# Sensors.net
KiCad netlist of a schematic drawn in Altium Designer
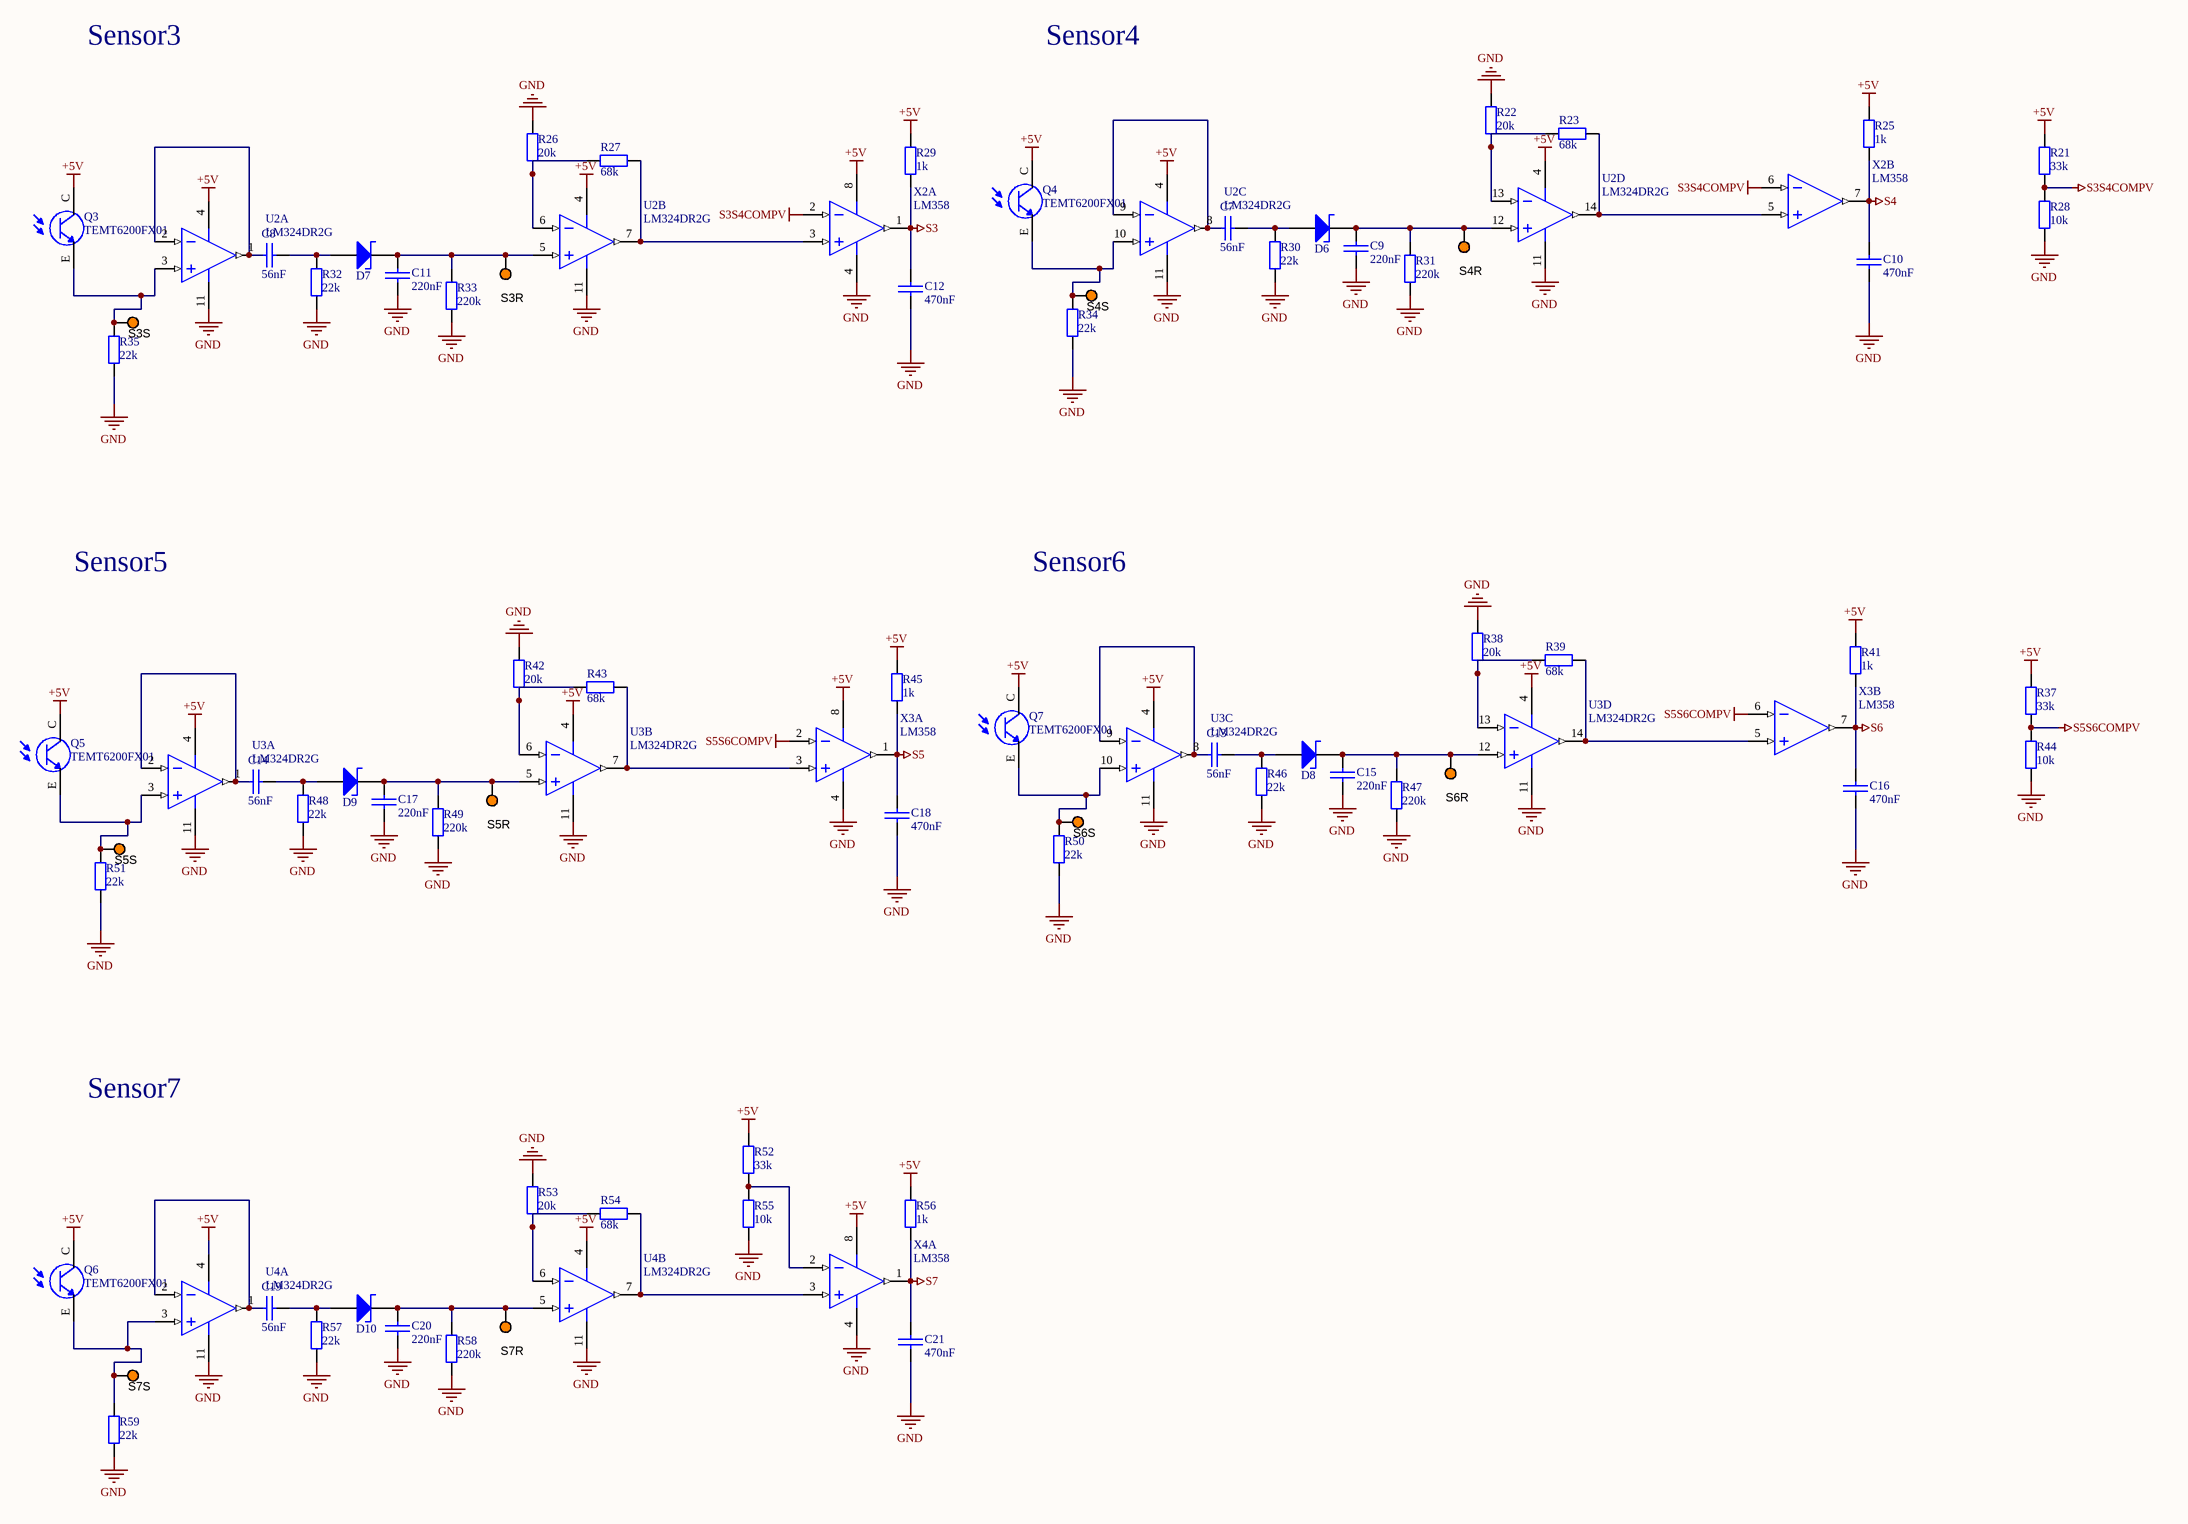
[diagram p0: Sensors.SchDoc]

(export (version "E")
  (design (tool "Eeschema 10.0.6"))
  (components
    (comp (ref "C7")
      (value "56nF")
      (footprint "0805 CAP")
      (description "SMT ceramic capacitor 0805 size")
      (libsource (lib "EE209_Library") (part "CerCap_SMT_0805"))
    )
    (comp (ref "C8")
      (value "56nF")
      (footprint "0805 CAP")
      (description "SMT ceramic capacitor 0805 size")
      (libsource (lib "EE209_Library") (part "CerCap_SMT_0805"))
    )
    (comp (ref "C9")
      (value "220nF")
      (footprint "0805 CAP")
      (description "SMT ceramic capacitor 0805 size")
      (libsource (lib "EE209_Library") (part "CerCap_SMT_0805"))
    )
    (comp (ref "C10")
      (value "470nF")
      (footprint "0805 CAP")
      (description "SMT ceramic capacitor 0805 size")
      (libsource (lib "EE209_Library") (part "CerCap_SMT_0805"))
    )
    (comp (ref "C11")
      (value "220nF")
      (footprint "0805 CAP")
      (description "SMT ceramic capacitor 0805 size")
      (libsource (lib "EE209_Library") (part "CerCap_SMT_0805"))
    )
    (comp (ref "C12")
      (value "470nF")
      (footprint "0805 CAP")
      (description "SMT ceramic capacitor 0805 size")
      (libsource (lib "EE209_Library") (part "CerCap_SMT_0805"))
    )
    (comp (ref "C13")
      (value "56nF")
      (footprint "0805 CAP")
      (description "SMT ceramic capacitor 0805 size")
      (libsource (lib "EE209_Library") (part "CerCap_SMT_0805"))
    )
    (comp (ref "C14")
      (value "56nF")
      (footprint "0805 CAP")
      (description "SMT ceramic capacitor 0805 size")
      (libsource (lib "EE209_Library") (part "CerCap_SMT_0805"))
    )
    (comp (ref "C15")
      (value "220nF")
      (footprint "0805 CAP")
      (description "SMT ceramic capacitor 0805 size")
      (libsource (lib "EE209_Library") (part "CerCap_SMT_0805"))
    )
    (comp (ref "C16")
      (value "470nF")
      (footprint "0805 CAP")
      (description "SMT ceramic capacitor 0805 size")
      (libsource (lib "EE209_Library") (part "CerCap_SMT_0805"))
    )
    (comp (ref "C17")
      (value "220nF")
      (footprint "0805 CAP")
      (description "SMT ceramic capacitor 0805 size")
      (libsource (lib "EE209_Library") (part "CerCap_SMT_0805"))
    )
    (comp (ref "C18")
      (value "470nF")
      (footprint "0805 CAP")
      (description "SMT ceramic capacitor 0805 size")
      (libsource (lib "EE209_Library") (part "CerCap_SMT_0805"))
    )
    (comp (ref "C19")
      (value "56nF")
      (footprint "0805 CAP")
      (description "SMT ceramic capacitor 0805 size")
      (libsource (lib "EE209_Library") (part "CerCap_SMT_0805"))
    )
    (comp (ref "C20")
      (value "220nF")
      (footprint "0805 CAP")
      (description "SMT ceramic capacitor 0805 size")
      (libsource (lib "EE209_Library") (part "CerCap_SMT_0805"))
    )
    (comp (ref "C21")
      (value "470nF")
      (footprint "0805 CAP")
      (description "SMT ceramic capacitor 0805 size")
      (libsource (lib "EE209_Library") (part "CerCap_SMT_0805"))
    )
    (comp (ref "D6")
      (value "BZT52H-B4V7")
      (footprint "SOD123")
      (description "SMT zener diode with SOD123 package")
      (fields
        (field (name "MANUFACTURER") "Nexperia USA Inc.")
        (field (name "MANUFACTURER PART NUMBER") "BZT52H-B4V7,115")
      )
      (libsource (lib "EE209_Library") (part "Zener_SMT_SOD123"))
    )
    (comp (ref "D7")
      (value "BZT52H-B4V7")
      (footprint "SOD123")
      (description "SMT zener diode with SOD123 package")
      (fields
        (field (name "MANUFACTURER") "Nexperia USA Inc.")
        (field (name "MANUFACTURER PART NUMBER") "BZT52H-B4V7,115")
      )
      (libsource (lib "EE209_Library") (part "Zener_SMT_SOD123"))
    )
    (comp (ref "D8")
      (value "BZT52H-B4V7")
      (footprint "SOD123")
      (description "SMT zener diode with SOD123 package")
      (fields
        (field (name "MANUFACTURER") "Nexperia USA Inc.")
        (field (name "MANUFACTURER PART NUMBER") "BZT52H-B4V7,115")
      )
      (libsource (lib "EE209_Library") (part "Zener_SMT_SOD123"))
    )
    (comp (ref "D9")
      (value "BZT52H-B4V7")
      (footprint "SOD123")
      (description "SMT zener diode with SOD123 package")
      (fields
        (field (name "MANUFACTURER") "Nexperia USA Inc.")
        (field (name "MANUFACTURER PART NUMBER") "BZT52H-B4V7,115")
      )
      (libsource (lib "EE209_Library") (part "Zener_SMT_SOD123"))
    )
    (comp (ref "D10")
      (value "BZT52H-B4V7")
      (footprint "SOD123")
      (description "SMT zener diode with SOD123 package")
      (fields
        (field (name "MANUFACTURER") "Nexperia USA Inc.")
        (field (name "MANUFACTURER PART NUMBER") "BZT52H-B4V7,115")
      )
      (libsource (lib "EE209_Library") (part "Zener_SMT_SOD123"))
    )
    (comp (ref "Q3")
      (value "TEMT6200FX01")
      (footprint "XDCR_TEMT6200FX01")
      (description "Phototransistors 550nm Top View 0805 (2012 Metric)")
      (fields (field (name "MF") "Vishay Semiconductor"))
      (libsource (lib "TEMT6200FX01") (part "TEMT6200FX01"))
    )
    (comp (ref "Q4")
      (value "TEMT6200FX01")
      (footprint "XDCR_TEMT6200FX01")
      (description "Phototransistors 550nm Top View 0805 (2012 Metric)")
      (fields (field (name "MF") "Vishay Semiconductor"))
      (libsource (lib "TEMT6200FX01") (part "TEMT6200FX01"))
    )
    (comp (ref "Q5")
      (value "TEMT6200FX01")
      (footprint "XDCR_TEMT6200FX01")
      (description "Phototransistors 550nm Top View 0805 (2012 Metric)")
      (fields (field (name "MF") "Vishay Semiconductor"))
      (libsource (lib "TEMT6200FX01") (part "TEMT6200FX01"))
    )
    (comp (ref "Q6")
      (value "TEMT6200FX01")
      (footprint "XDCR_TEMT6200FX01")
      (description "Phototransistors 550nm Top View 0805 (2012 Metric)")
      (fields (field (name "MF") "Vishay Semiconductor"))
      (libsource (lib "TEMT6200FX01") (part "TEMT6200FX01"))
    )
    (comp (ref "Q7")
      (value "TEMT6200FX01")
      (footprint "XDCR_TEMT6200FX01")
      (description "Phototransistors 550nm Top View 0805 (2012 Metric)")
      (fields (field (name "MF") "Vishay Semiconductor"))
      (libsource (lib "TEMT6200FX01") (part "TEMT6200FX01"))
    )
    (comp (ref "R21")
      (value "33k")
      (footprint "0805 RES")
      (description "0805 resistor")
      (fields (field (name "PUBLISHER") "Altium Limited"))
      (libsource (lib "") (part "Res_SMT_0805_2"))
    )
    (comp (ref "R22")
      (value "20k")
      (footprint "0805 RES")
      (description "0805 resistor")
      (fields (field (name "PUBLISHER") "Altium Limited"))
      (libsource (lib "EE209_Library") (part "Res_SMT_0805"))
    )
    (comp (ref "R23")
      (value "68k")
      (footprint "0805 RES")
      (description "0805 resistor")
      (fields (field (name "PUBLISHER") "Altium Limited"))
      (libsource (lib "") (part "Res_SMT_0805_1"))
    )
    (comp (ref "R25")
      (value "1k")
      (footprint "0805 RES")
      (description "0805 resistor")
      (fields (field (name "PUBLISHER") "Altium Limited"))
      (libsource (lib "") (part "Res_SMT_0805_2"))
    )
    (comp (ref "R26")
      (value "20k")
      (footprint "0805 RES")
      (description "0805 resistor")
      (fields (field (name "PUBLISHER") "Altium Limited"))
      (libsource (lib "EE209_Library") (part "Res_SMT_0805"))
    )
    (comp (ref "R27")
      (value "68k")
      (footprint "0805 RES")
      (description "0805 resistor")
      (fields (field (name "PUBLISHER") "Altium Limited"))
      (libsource (lib "") (part "Res_SMT_0805_1"))
    )
    (comp (ref "R28")
      (value "10k")
      (footprint "0805 RES")
      (description "0805 resistor")
      (fields (field (name "PUBLISHER") "Altium Limited"))
      (libsource (lib "") (part "Res_SMT_0805_2"))
    )
    (comp (ref "R29")
      (value "1k")
      (footprint "0805 RES")
      (description "0805 resistor")
      (fields (field (name "PUBLISHER") "Altium Limited"))
      (libsource (lib "") (part "Res_SMT_0805_2"))
    )
    (comp (ref "R30")
      (value "22k")
      (footprint "0805 RES")
      (description "0805 resistor")
      (fields (field (name "PUBLISHER") "Altium Limited"))
      (libsource (lib "EE209_Library") (part "Res_SMT_0805"))
    )
    (comp (ref "R31")
      (value "220k")
      (footprint "0805 RES")
      (description "0805 resistor")
      (fields (field (name "PUBLISHER") "Altium Limited"))
      (libsource (lib "EE209_Library") (part "Res_SMT_0805"))
    )
    (comp (ref "R32")
      (value "22k")
      (footprint "0805 RES")
      (description "0805 resistor")
      (fields (field (name "PUBLISHER") "Altium Limited"))
      (libsource (lib "EE209_Library") (part "Res_SMT_0805"))
    )
    (comp (ref "R33")
      (value "220k")
      (footprint "0805 RES")
      (description "0805 resistor")
      (fields (field (name "PUBLISHER") "Altium Limited"))
      (libsource (lib "EE209_Library") (part "Res_SMT_0805"))
    )
    (comp (ref "R34")
      (value "22k")
      (footprint "0805 RES")
      (description "0805 resistor")
      (fields (field (name "PUBLISHER") "Altium Limited"))
      (libsource (lib "EE209_Library") (part "Res_SMT_0805"))
    )
    (comp (ref "R35")
      (value "22k")
      (footprint "0805 RES")
      (description "0805 resistor")
      (fields (field (name "PUBLISHER") "Altium Limited"))
      (libsource (lib "EE209_Library") (part "Res_SMT_0805"))
    )
    (comp (ref "R37")
      (value "33k")
      (footprint "0805 RES")
      (description "0805 resistor")
      (fields (field (name "PUBLISHER") "Altium Limited"))
      (libsource (lib "") (part "Res_SMT_0805_2"))
    )
    (comp (ref "R38")
      (value "20k")
      (footprint "0805 RES")
      (description "0805 resistor")
      (fields (field (name "PUBLISHER") "Altium Limited"))
      (libsource (lib "EE209_Library") (part "Res_SMT_0805"))
    )
    (comp (ref "R39")
      (value "68k")
      (footprint "0805 RES")
      (description "0805 resistor")
      (fields (field (name "PUBLISHER") "Altium Limited"))
      (libsource (lib "") (part "Res_SMT_0805_1"))
    )
    (comp (ref "R41")
      (value "1k")
      (footprint "0805 RES")
      (description "0805 resistor")
      (fields (field (name "PUBLISHER") "Altium Limited"))
      (libsource (lib "") (part "Res_SMT_0805_2"))
    )
    (comp (ref "R42")
      (value "20k")
      (footprint "0805 RES")
      (description "0805 resistor")
      (fields (field (name "PUBLISHER") "Altium Limited"))
      (libsource (lib "EE209_Library") (part "Res_SMT_0805"))
    )
    (comp (ref "R43")
      (value "68k")
      (footprint "0805 RES")
      (description "0805 resistor")
      (fields (field (name "PUBLISHER") "Altium Limited"))
      (libsource (lib "") (part "Res_SMT_0805_1"))
    )
    (comp (ref "R44")
      (value "10k")
      (footprint "0805 RES")
      (description "0805 resistor")
      (fields (field (name "PUBLISHER") "Altium Limited"))
      (libsource (lib "") (part "Res_SMT_0805_2"))
    )
    (comp (ref "R45")
      (value "1k")
      (footprint "0805 RES")
      (description "0805 resistor")
      (fields (field (name "PUBLISHER") "Altium Limited"))
      (libsource (lib "") (part "Res_SMT_0805_2"))
    )
    (comp (ref "R46")
      (value "22k")
      (footprint "0805 RES")
      (description "0805 resistor")
      (fields (field (name "PUBLISHER") "Altium Limited"))
      (libsource (lib "EE209_Library") (part "Res_SMT_0805"))
    )
    (comp (ref "R47")
      (value "220k")
      (footprint "0805 RES")
      (description "0805 resistor")
      (fields (field (name "PUBLISHER") "Altium Limited"))
      (libsource (lib "EE209_Library") (part "Res_SMT_0805"))
    )
    (comp (ref "R48")
      (value "22k")
      (footprint "0805 RES")
      (description "0805 resistor")
      (fields (field (name "PUBLISHER") "Altium Limited"))
      (libsource (lib "EE209_Library") (part "Res_SMT_0805"))
    )
    (comp (ref "R49")
      (value "220k")
      (footprint "0805 RES")
      (description "0805 resistor")
      (fields (field (name "PUBLISHER") "Altium Limited"))
      (libsource (lib "EE209_Library") (part "Res_SMT_0805"))
    )
    (comp (ref "R50")
      (value "22k")
      (footprint "0805 RES")
      (description "0805 resistor")
      (fields (field (name "PUBLISHER") "Altium Limited"))
      (libsource (lib "EE209_Library") (part "Res_SMT_0805"))
    )
    (comp (ref "R51")
      (value "22k")
      (footprint "0805 RES")
      (description "0805 resistor")
      (fields (field (name "PUBLISHER") "Altium Limited"))
      (libsource (lib "EE209_Library") (part "Res_SMT_0805"))
    )
    (comp (ref "R52")
      (value "33k")
      (footprint "0805 RES")
      (description "0805 resistor")
      (fields (field (name "PUBLISHER") "Altium Limited"))
      (libsource (lib "") (part "Res_SMT_0805_2"))
    )
    (comp (ref "R53")
      (value "20k")
      (footprint "0805 RES")
      (description "0805 resistor")
      (fields (field (name "PUBLISHER") "Altium Limited"))
      (libsource (lib "EE209_Library") (part "Res_SMT_0805"))
    )
    (comp (ref "R54")
      (value "68k")
      (footprint "0805 RES")
      (description "0805 resistor")
      (fields (field (name "PUBLISHER") "Altium Limited"))
      (libsource (lib "") (part "Res_SMT_0805_1"))
    )
    (comp (ref "R55")
      (value "10k")
      (footprint "0805 RES")
      (description "0805 resistor")
      (fields (field (name "PUBLISHER") "Altium Limited"))
      (libsource (lib "") (part "Res_SMT_0805_2"))
    )
    (comp (ref "R56")
      (value "1k")
      (footprint "0805 RES")
      (description "0805 resistor")
      (fields (field (name "PUBLISHER") "Altium Limited"))
      (libsource (lib "") (part "Res_SMT_0805_2"))
    )
    (comp (ref "R57")
      (value "22k")
      (footprint "0805 RES")
      (description "0805 resistor")
      (fields (field (name "PUBLISHER") "Altium Limited"))
      (libsource (lib "EE209_Library") (part "Res_SMT_0805"))
    )
    (comp (ref "R58")
      (value "220k")
      (footprint "0805 RES")
      (description "0805 resistor")
      (fields (field (name "PUBLISHER") "Altium Limited"))
      (libsource (lib "EE209_Library") (part "Res_SMT_0805"))
    )
    (comp (ref "R59")
      (value "22k")
      (footprint "0805 RES")
      (description "0805 resistor")
      (fields (field (name "PUBLISHER") "Altium Limited"))
      (libsource (lib "EE209_Library") (part "Res_SMT_0805"))
    )
    (comp (ref "S3R")
      (value "5003")
      (footprint "TP_TH")
      (description "Test Point, Orange, 1-Pin THD, RoHS")
      (libsource (lib "EE209_Library") (part "TestPoint"))
    )
    (comp (ref "S3S")
      (value "5003")
      (footprint "TP_TH")
      (description "Test Point, Orange, 1-Pin THD, RoHS")
      (libsource (lib "EE209_Library") (part "TestPoint"))
    )
    (comp (ref "S4R")
      (value "5003")
      (footprint "TP_TH")
      (description "Test Point, Orange, 1-Pin THD, RoHS")
      (libsource (lib "EE209_Library") (part "TestPoint"))
    )
    (comp (ref "S4S")
      (value "5003")
      (footprint "TP_TH")
      (description "Test Point, Orange, 1-Pin THD, RoHS")
      (libsource (lib "EE209_Library") (part "TestPoint"))
    )
    (comp (ref "S5R")
      (value "5003")
      (footprint "TP_TH")
      (description "Test Point, Orange, 1-Pin THD, RoHS")
      (libsource (lib "EE209_Library") (part "TestPoint"))
    )
    (comp (ref "S5S")
      (value "5003")
      (footprint "TP_TH")
      (description "Test Point, Orange, 1-Pin THD, RoHS")
      (libsource (lib "EE209_Library") (part "TestPoint"))
    )
    (comp (ref "S6R")
      (value "5003")
      (footprint "TP_TH")
      (description "Test Point, Orange, 1-Pin THD, RoHS")
      (libsource (lib "EE209_Library") (part "TestPoint"))
    )
    (comp (ref "S6S")
      (value "5003")
      (footprint "TP_TH")
      (description "Test Point, Orange, 1-Pin THD, RoHS")
      (libsource (lib "EE209_Library") (part "TestPoint"))
    )
    (comp (ref "S7R")
      (value "5003")
      (footprint "TP_TH")
      (description "Test Point, Orange, 1-Pin THD, RoHS")
      (libsource (lib "EE209_Library") (part "TestPoint"))
    )
    (comp (ref "S7S")
      (value "5003")
      (footprint "TP_TH")
      (description "Test Point, Orange, 1-Pin THD, RoHS")
      (libsource (lib "EE209_Library") (part "TestPoint"))
    )
    (comp (ref "U2")
      (value "LM324DR2G")
      (footprint "SOIC-14")
      (fields (field (name "MANUFACTURER") "On Semiconductor"))
      (libsource (lib "EE209_Library") (part "LM324DR_SMT_SOIC16"))
    )
    (comp (ref "U3")
      (value "LM324DR2G")
      (footprint "SOIC-14")
      (fields (field (name "MANUFACTURER") "On Semiconductor"))
      (libsource (lib "EE209_Library") (part "LM324DR_SMT_SOIC16"))
    )
    (comp (ref "U4")
      (value "LM324DR2G")
      (footprint "SOIC-14")
      (fields (field (name "MANUFACTURER") "On Semiconductor"))
      (libsource (lib "EE209_Library") (part "LM324DR_SMT_SOIC16"))
    )
    (comp (ref "X2")
      (value "LM358")
      (footprint "SO - 8")
      (description "IC OPAMP 8SOIC")
      (libsource (lib "EE209_Library") (part "LM358_SMT_SOIC8"))
    )
    (comp (ref "X3")
      (value "LM358")
      (footprint "SO - 8")
      (description "IC OPAMP 8SOIC")
      (libsource (lib "EE209_Library") (part "LM358_SMT_SOIC8"))
    )
    (comp (ref "X4")
      (value "LM358")
      (footprint "SO - 8")
      (description "IC OPAMP 8SOIC")
      (libsource (lib "EE209_Library") (part "LM358_SMT_SOIC8"))
    )
  )
  (nets
    (net (code "1") (name "+5V") (class "Default")
      (node (ref "Q3") (pin "C") (pinfunction "C_C") (pintype "passive"))
      (node (ref "Q4") (pin "C") (pinfunction "C_C") (pintype "passive"))
      (node (ref "Q5") (pin "C") (pinfunction "C_C") (pintype "passive"))
      (node (ref "Q6") (pin "C") (pinfunction "C_C") (pintype "passive"))
      (node (ref "Q7") (pin "C") (pinfunction "C_C") (pintype "passive"))
      (node (ref "R21") (pin "1") (pinfunction "1_1") (pintype "passive"))
      (node (ref "R25") (pin "1") (pinfunction "1_1") (pintype "passive"))
      (node (ref "R29") (pin "1") (pinfunction "1_1") (pintype "passive"))
      (node (ref "R37") (pin "1") (pinfunction "1_1") (pintype "passive"))
      (node (ref "R41") (pin "1") (pinfunction "1_1") (pintype "passive"))
      (node (ref "R45") (pin "1") (pinfunction "1_1") (pintype "passive"))
      (node (ref "R52") (pin "1") (pinfunction "1_1") (pintype "passive"))
      (node (ref "R56") (pin "1") (pinfunction "1_1") (pintype "passive"))
      (node (ref "U2") (pin "4") (pinfunction "VCC_4") (pintype "power_in"))
      (node (ref "U3") (pin "4") (pinfunction "VCC_4") (pintype "power_in"))
      (node (ref "U4") (pin "4") (pinfunction "VCC_4") (pintype "power_in"))
      (node (ref "X2") (pin "8") (pinfunction "VDD_8") (pintype "power_in"))
      (node (ref "X3") (pin "8") (pinfunction "VDD_8") (pintype "power_in"))
      (node (ref "X4") (pin "8") (pinfunction "VDD_8") (pintype "power_in"))
    )
    (net (code "2") (name "GND") (class "Default")
      (node (ref "C10") (pin "2") (pinfunction "2_2") (pintype "passive"))
      (node (ref "C11") (pin "2") (pinfunction "2_2") (pintype "passive"))
      (node (ref "C12") (pin "2") (pinfunction "2_2") (pintype "passive"))
      (node (ref "C15") (pin "2") (pinfunction "2_2") (pintype "passive"))
      (node (ref "C16") (pin "2") (pinfunction "2_2") (pintype "passive"))
      (node (ref "C17") (pin "2") (pinfunction "2_2") (pintype "passive"))
      (node (ref "C18") (pin "2") (pinfunction "2_2") (pintype "passive"))
      (node (ref "C20") (pin "2") (pinfunction "2_2") (pintype "passive"))
      (node (ref "C21") (pin "2") (pinfunction "2_2") (pintype "passive"))
      (node (ref "C9") (pin "2") (pinfunction "2_2") (pintype "passive"))
      (node (ref "R22") (pin "2") (pinfunction "2_2") (pintype "passive"))
      (node (ref "R26") (pin "2") (pinfunction "2_2") (pintype "passive"))
      (node (ref "R28") (pin "2") (pinfunction "2_2") (pintype "passive"))
      (node (ref "R30") (pin "1") (pinfunction "1_1") (pintype "passive"))
      (node (ref "R31") (pin "1") (pinfunction "1_1") (pintype "passive"))
      (node (ref "R32") (pin "1") (pinfunction "1_1") (pintype "passive"))
      (node (ref "R33") (pin "1") (pinfunction "1_1") (pintype "passive"))
      (node (ref "R34") (pin "1") (pinfunction "1_1") (pintype "passive"))
      (node (ref "R35") (pin "1") (pinfunction "1_1") (pintype "passive"))
      (node (ref "R38") (pin "2") (pinfunction "2_2") (pintype "passive"))
      (node (ref "R42") (pin "2") (pinfunction "2_2") (pintype "passive"))
      (node (ref "R44") (pin "2") (pinfunction "2_2") (pintype "passive"))
      (node (ref "R46") (pin "1") (pinfunction "1_1") (pintype "passive"))
      (node (ref "R47") (pin "1") (pinfunction "1_1") (pintype "passive"))
      (node (ref "R48") (pin "1") (pinfunction "1_1") (pintype "passive"))
      (node (ref "R49") (pin "1") (pinfunction "1_1") (pintype "passive"))
      (node (ref "R50") (pin "1") (pinfunction "1_1") (pintype "passive"))
      (node (ref "R51") (pin "1") (pinfunction "1_1") (pintype "passive"))
      (node (ref "R53") (pin "2") (pinfunction "2_2") (pintype "passive"))
      (node (ref "R55") (pin "2") (pinfunction "2_2") (pintype "passive"))
      (node (ref "R57") (pin "1") (pinfunction "1_1") (pintype "passive"))
      (node (ref "R58") (pin "1") (pinfunction "1_1") (pintype "passive"))
      (node (ref "R59") (pin "1") (pinfunction "1_1") (pintype "passive"))
      (node (ref "U2") (pin "11") (pinfunction "VEE/GND_11") (pintype "power_in"))
      (node (ref "U3") (pin "11") (pinfunction "VEE/GND_11") (pintype "power_in"))
      (node (ref "U4") (pin "11") (pinfunction "VEE/GND_11") (pintype "power_in"))
      (node (ref "X2") (pin "4") (pinfunction "VSS_4") (pintype "power_in"))
      (node (ref "X3") (pin "4") (pinfunction "VSS_4") (pintype "power_in"))
      (node (ref "X4") (pin "4") (pinfunction "VSS_4") (pintype "power_in"))
    )
    (net (code "3") (name "Net-(D6-A)") (class "Default")
      (node (ref "C7") (pin "2") (pinfunction "2_2") (pintype "passive"))
      (node (ref "D6") (pin "1") (pinfunction "A_1") (pintype "passive"))
      (node (ref "R30") (pin "2") (pinfunction "2_2") (pintype "passive"))
    )
    (net (code "4") (name "Net-(D6-K)") (class "Default")
      (node (ref "C9") (pin "1") (pinfunction "1_1") (pintype "passive"))
      (node (ref "D6") (pin "2") (pinfunction "K_2") (pintype "passive"))
      (node (ref "R31") (pin "2") (pinfunction "2_2") (pintype "passive"))
      (node (ref "S4R") (pin "1") (pinfunction "1_1") (pintype "passive"))
      (node (ref "U2") (pin "12") (pinfunction "IN4+_12") (pintype "input"))
    )
    (net (code "5") (name "Net-(D7-A)") (class "Default")
      (node (ref "C8") (pin "2") (pinfunction "2_2") (pintype "passive"))
      (node (ref "D7") (pin "1") (pinfunction "A_1") (pintype "passive"))
      (node (ref "R32") (pin "2") (pinfunction "2_2") (pintype "passive"))
    )
    (net (code "6") (name "Net-(D7-K)") (class "Default")
      (node (ref "C11") (pin "1") (pinfunction "1_1") (pintype "passive"))
      (node (ref "D7") (pin "2") (pinfunction "K_2") (pintype "passive"))
      (node (ref "R33") (pin "2") (pinfunction "2_2") (pintype "passive"))
      (node (ref "S3R") (pin "1") (pinfunction "1_1") (pintype "passive"))
      (node (ref "U2") (pin "5") (pinfunction "IN2+_5") (pintype "input"))
    )
    (net (code "7") (name "Net-(D8-A)") (class "Default")
      (node (ref "C13") (pin "2") (pinfunction "2_2") (pintype "passive"))
      (node (ref "D8") (pin "1") (pinfunction "A_1") (pintype "passive"))
      (node (ref "R46") (pin "2") (pinfunction "2_2") (pintype "passive"))
    )
    (net (code "8") (name "Net-(D8-K)") (class "Default")
      (node (ref "C15") (pin "1") (pinfunction "1_1") (pintype "passive"))
      (node (ref "D8") (pin "2") (pinfunction "K_2") (pintype "passive"))
      (node (ref "R47") (pin "2") (pinfunction "2_2") (pintype "passive"))
      (node (ref "S6R") (pin "1") (pinfunction "1_1") (pintype "passive"))
      (node (ref "U3") (pin "12") (pinfunction "IN4+_12") (pintype "input"))
    )
    (net (code "9") (name "Net-(D9-A)") (class "Default")
      (node (ref "C14") (pin "2") (pinfunction "2_2") (pintype "passive"))
      (node (ref "D9") (pin "1") (pinfunction "A_1") (pintype "passive"))
      (node (ref "R48") (pin "2") (pinfunction "2_2") (pintype "passive"))
    )
    (net (code "10") (name "Net-(D9-K)") (class "Default")
      (node (ref "C17") (pin "1") (pinfunction "1_1") (pintype "passive"))
      (node (ref "D9") (pin "2") (pinfunction "K_2") (pintype "passive"))
      (node (ref "R49") (pin "2") (pinfunction "2_2") (pintype "passive"))
      (node (ref "S5R") (pin "1") (pinfunction "1_1") (pintype "passive"))
      (node (ref "U3") (pin "5") (pinfunction "IN2+_5") (pintype "input"))
    )
    (net (code "11") (name "Net-(D10-A)") (class "Default")
      (node (ref "C19") (pin "2") (pinfunction "2_2") (pintype "passive"))
      (node (ref "D10") (pin "1") (pinfunction "A_1") (pintype "passive"))
      (node (ref "R57") (pin "2") (pinfunction "2_2") (pintype "passive"))
    )
    (net (code "12") (name "Net-(D10-K)") (class "Default")
      (node (ref "C20") (pin "1") (pinfunction "1_1") (pintype "passive"))
      (node (ref "D10") (pin "2") (pinfunction "K_2") (pintype "passive"))
      (node (ref "R58") (pin "2") (pinfunction "2_2") (pintype "passive"))
      (node (ref "S7R") (pin "1") (pinfunction "1_1") (pintype "passive"))
      (node (ref "U4") (pin "5") (pinfunction "IN2+_5") (pintype "input"))
    )
    (net (code "13") (name "Net-(U2A-IN1+)") (class "Default")
      (node (ref "Q3") (pin "E") (pinfunction "E_E") (pintype "passive"))
      (node (ref "R35") (pin "2") (pinfunction "2_2") (pintype "passive"))
      (node (ref "S3S") (pin "1") (pinfunction "1_1") (pintype "passive"))
      (node (ref "U2") (pin "3") (pinfunction "IN1+_3") (pintype "input"))
    )
    (net (code "14") (name "Net-(U2A-IN1-)") (class "Default")
      (node (ref "C8") (pin "1") (pinfunction "1_1") (pintype "passive"))
      (node (ref "U2") (pin "1") (pinfunction "OUT1_1") (pintype "output"))
      (node (ref "U2") (pin "2") (pinfunction "IN1-_2") (pintype "input"))
    )
    (net (code "15") (name "Net-(U2B-IN2-)") (class "Default")
      (node (ref "R26") (pin "1") (pinfunction "1_1") (pintype "passive"))
      (node (ref "R27") (pin "2") (pinfunction "2_2") (pintype "passive"))
      (node (ref "U2") (pin "6") (pinfunction "IN2-_6") (pintype "input"))
    )
    (net (code "16") (name "Net-(U2B-OUT2)") (class "Default")
      (node (ref "R27") (pin "1") (pinfunction "1_1") (pintype "passive"))
      (node (ref "U2") (pin "7") (pinfunction "OUT2_7") (pintype "output"))
      (node (ref "X2") (pin "3") (pinfunction "VINA+_3") (pintype "input"))
    )
    (net (code "17") (name "Net-(U2C-IN3+)") (class "Default")
      (node (ref "Q4") (pin "E") (pinfunction "E_E") (pintype "passive"))
      (node (ref "R34") (pin "2") (pinfunction "2_2") (pintype "passive"))
      (node (ref "S4S") (pin "1") (pinfunction "1_1") (pintype "passive"))
      (node (ref "U2") (pin "10") (pinfunction "IN3+_10") (pintype "input"))
    )
    (net (code "18") (name "Net-(U2C-IN3-)") (class "Default")
      (node (ref "C7") (pin "1") (pinfunction "1_1") (pintype "passive"))
      (node (ref "U2") (pin "8") (pinfunction "OUT3_8") (pintype "output"))
      (node (ref "U2") (pin "9") (pinfunction "IN3-_9") (pintype "input"))
    )
    (net (code "19") (name "Net-(U2D-IN4-)") (class "Default")
      (node (ref "R22") (pin "1") (pinfunction "1_1") (pintype "passive"))
      (node (ref "R23") (pin "2") (pinfunction "2_2") (pintype "passive"))
      (node (ref "U2") (pin "13") (pinfunction "IN4-_13") (pintype "input"))
    )
    (net (code "20") (name "Net-(U2D-OUT4)") (class "Default")
      (node (ref "R23") (pin "1") (pinfunction "1_1") (pintype "passive"))
      (node (ref "U2") (pin "14") (pinfunction "OUT4_14") (pintype "output"))
      (node (ref "X2") (pin "5") (pinfunction "VINA+_5") (pintype "input"))
    )
    (net (code "21") (name "Net-(U3A-IN1+)") (class "Default")
      (node (ref "Q5") (pin "E") (pinfunction "E_E") (pintype "passive"))
      (node (ref "R51") (pin "2") (pinfunction "2_2") (pintype "passive"))
      (node (ref "S5S") (pin "1") (pinfunction "1_1") (pintype "passive"))
      (node (ref "U3") (pin "3") (pinfunction "IN1+_3") (pintype "input"))
    )
    (net (code "22") (name "Net-(U3A-IN1-)") (class "Default")
      (node (ref "C14") (pin "1") (pinfunction "1_1") (pintype "passive"))
      (node (ref "U3") (pin "1") (pinfunction "OUT1_1") (pintype "output"))
      (node (ref "U3") (pin "2") (pinfunction "IN1-_2") (pintype "input"))
    )
    (net (code "23") (name "Net-(U3B-IN2-)") (class "Default")
      (node (ref "R42") (pin "1") (pinfunction "1_1") (pintype "passive"))
      (node (ref "R43") (pin "2") (pinfunction "2_2") (pintype "passive"))
      (node (ref "U3") (pin "6") (pinfunction "IN2-_6") (pintype "input"))
    )
    (net (code "24") (name "Net-(U3B-OUT2)") (class "Default")
      (node (ref "R43") (pin "1") (pinfunction "1_1") (pintype "passive"))
      (node (ref "U3") (pin "7") (pinfunction "OUT2_7") (pintype "output"))
      (node (ref "X3") (pin "3") (pinfunction "VINA+_3") (pintype "input"))
    )
    (net (code "25") (name "Net-(U3C-IN3+)") (class "Default")
      (node (ref "Q7") (pin "E") (pinfunction "E_E") (pintype "passive"))
      (node (ref "R50") (pin "2") (pinfunction "2_2") (pintype "passive"))
      (node (ref "S6S") (pin "1") (pinfunction "1_1") (pintype "passive"))
      (node (ref "U3") (pin "10") (pinfunction "IN3+_10") (pintype "input"))
    )
    (net (code "26") (name "Net-(U3C-IN3-)") (class "Default")
      (node (ref "C13") (pin "1") (pinfunction "1_1") (pintype "passive"))
      (node (ref "U3") (pin "8") (pinfunction "OUT3_8") (pintype "output"))
      (node (ref "U3") (pin "9") (pinfunction "IN3-_9") (pintype "input"))
    )
    (net (code "27") (name "Net-(U3D-IN4-)") (class "Default")
      (node (ref "R38") (pin "1") (pinfunction "1_1") (pintype "passive"))
      (node (ref "R39") (pin "2") (pinfunction "2_2") (pintype "passive"))
      (node (ref "U3") (pin "13") (pinfunction "IN4-_13") (pintype "input"))
    )
    (net (code "28") (name "Net-(U3D-OUT4)") (class "Default")
      (node (ref "R39") (pin "1") (pinfunction "1_1") (pintype "passive"))
      (node (ref "U3") (pin "14") (pinfunction "OUT4_14") (pintype "output"))
      (node (ref "X3") (pin "5") (pinfunction "VINA+_5") (pintype "input"))
    )
    (net (code "29") (name "Net-(U4A-IN1+)") (class "Default")
      (node (ref "Q6") (pin "E") (pinfunction "E_E") (pintype "passive"))
      (node (ref "R59") (pin "2") (pinfunction "2_2") (pintype "passive"))
      (node (ref "S7S") (pin "1") (pinfunction "1_1") (pintype "passive"))
      (node (ref "U4") (pin "3") (pinfunction "IN1+_3") (pintype "input"))
    )
    (net (code "30") (name "Net-(U4A-IN1-)") (class "Default")
      (node (ref "C19") (pin "1") (pinfunction "1_1") (pintype "passive"))
      (node (ref "U4") (pin "1") (pinfunction "OUT1_1") (pintype "output"))
      (node (ref "U4") (pin "2") (pinfunction "IN1-_2") (pintype "input"))
    )
    (net (code "31") (name "Net-(U4B-IN2-)") (class "Default")
      (node (ref "R53") (pin "1") (pinfunction "1_1") (pintype "passive"))
      (node (ref "R54") (pin "2") (pinfunction "2_2") (pintype "passive"))
      (node (ref "U4") (pin "6") (pinfunction "IN2-_6") (pintype "input"))
    )
    (net (code "32") (name "Net-(U4B-OUT2)") (class "Default")
      (node (ref "R54") (pin "1") (pinfunction "1_1") (pintype "passive"))
      (node (ref "U4") (pin "7") (pinfunction "OUT2_7") (pintype "output"))
      (node (ref "X4") (pin "3") (pinfunction "VINA+_3") (pintype "input"))
    )
    (net (code "33") (name "Net-(X4A-VINA-)") (class "Default")
      (node (ref "R52") (pin "2") (pinfunction "2_2") (pintype "passive"))
      (node (ref "R55") (pin "1") (pinfunction "1_1") (pintype "passive"))
      (node (ref "X4") (pin "2") (pinfunction "VINA-_2") (pintype "input"))
    )
    (net (code "34") (name "S3") (class "Default")
      (node (ref "C12") (pin "1") (pinfunction "1_1") (pintype "passive"))
      (node (ref "R29") (pin "2") (pinfunction "2_2") (pintype "passive"))
      (node (ref "X2") (pin "1") (pinfunction "VOUTA_1") (pintype "output"))
    )
    (net (code "35") (name "S3S4COMPV") (class "Default")
      (node (ref "R21") (pin "2") (pinfunction "2_2") (pintype "passive"))
      (node (ref "R28") (pin "1") (pinfunction "1_1") (pintype "passive"))
      (node (ref "X2") (pin "2") (pinfunction "VINA-_2") (pintype "input"))
      (node (ref "X2") (pin "6") (pinfunction "VINA-_6") (pintype "input"))
    )
    (net (code "36") (name "S4") (class "Default")
      (node (ref "C10") (pin "1") (pinfunction "1_1") (pintype "passive"))
      (node (ref "R25") (pin "2") (pinfunction "2_2") (pintype "passive"))
      (node (ref "X2") (pin "7") (pinfunction "VOUTA_7") (pintype "output"))
    )
    (net (code "37") (name "S5") (class "Default")
      (node (ref "C18") (pin "1") (pinfunction "1_1") (pintype "passive"))
      (node (ref "R45") (pin "2") (pinfunction "2_2") (pintype "passive"))
      (node (ref "X3") (pin "1") (pinfunction "VOUTA_1") (pintype "output"))
    )
    (net (code "38") (name "S5S6COMPV") (class "Default")
      (node (ref "R37") (pin "2") (pinfunction "2_2") (pintype "passive"))
      (node (ref "R44") (pin "1") (pinfunction "1_1") (pintype "passive"))
      (node (ref "X3") (pin "2") (pinfunction "VINA-_2") (pintype "input"))
      (node (ref "X3") (pin "6") (pinfunction "VINA-_6") (pintype "input"))
    )
    (net (code "39") (name "S6") (class "Default")
      (node (ref "C16") (pin "1") (pinfunction "1_1") (pintype "passive"))
      (node (ref "R41") (pin "2") (pinfunction "2_2") (pintype "passive"))
      (node (ref "X3") (pin "7") (pinfunction "VOUTA_7") (pintype "output"))
    )
    (net (code "40") (name "S7") (class "Default")
      (node (ref "C21") (pin "1") (pinfunction "1_1") (pintype "passive"))
      (node (ref "R56") (pin "2") (pinfunction "2_2") (pintype "passive"))
      (node (ref "X4") (pin "1") (pinfunction "VOUTA_1") (pintype "output"))
    )
  )
)
